# led.net
KiCad netlist of a schematic drawn in Altium Designer
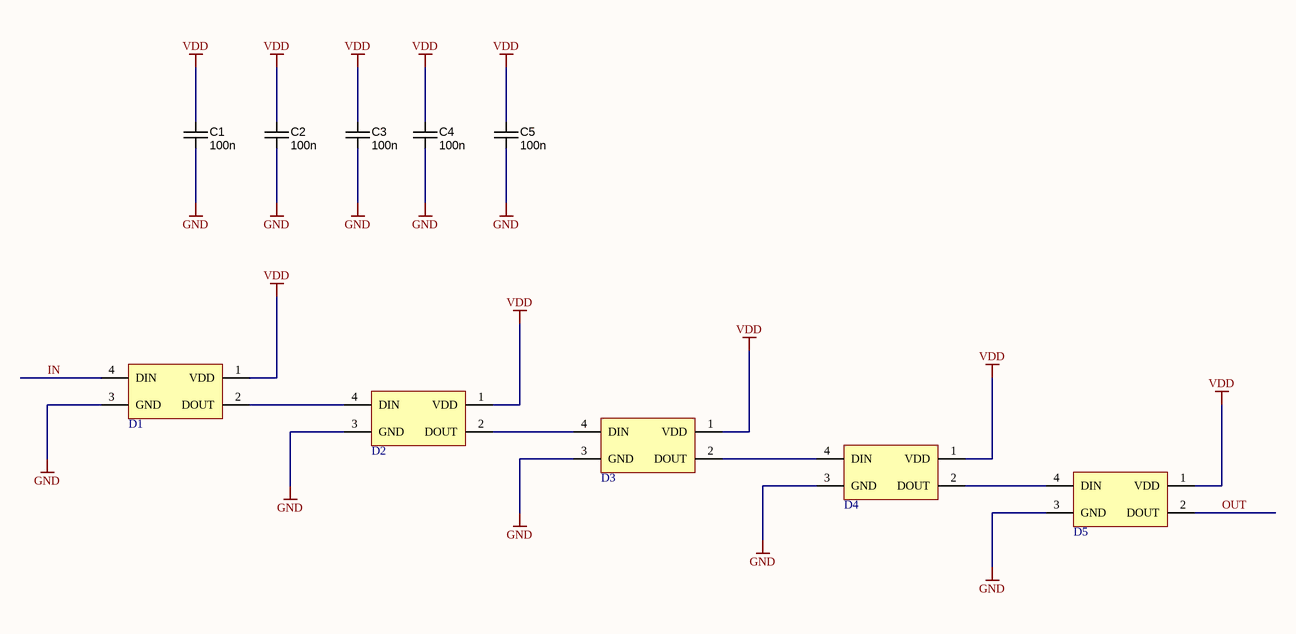
[diagram p0: led.SchDoc]

(export (version "E")
  (design (tool "Eeschema 10.0.6"))
  (components
    (comp (ref "C1")
      (value "100n")
      (footprint "CAPC1608X90N")
      (description "Capacitor SMD Cer 100nF 10% 50V X7R 0603")
      (fields (field (name "TOLERANCE") "±10%") (field (name "Comment") "approved sub OK"))
      (libsource (lib "PBL - Capacitors") (part "CAPC_100n_0603_X7R_50V_10%"))
    )
    (comp (ref "C2")
      (value "100n")
      (footprint "CAPC1608X90N")
      (description "Capacitor SMD Cer 100nF 10% 50V X7R 0603")
      (fields (field (name "TOLERANCE") "±10%") (field (name "Comment") "approved sub OK"))
      (libsource (lib "PBL - Capacitors") (part "CAPC_100n_0603_X7R_50V_10%"))
    )
    (comp (ref "C3")
      (value "100n")
      (footprint "CAPC1608X90N")
      (description "Capacitor SMD Cer 100nF 10% 50V X7R 0603")
      (fields (field (name "TOLERANCE") "±10%") (field (name "Comment") "approved sub OK"))
      (libsource (lib "PBL - Capacitors") (part "CAPC_100n_0603_X7R_50V_10%"))
    )
    (comp (ref "C4")
      (value "100n")
      (footprint "CAPC1608X90N")
      (description "Capacitor SMD Cer 100nF 10% 50V X7R 0603")
      (fields (field (name "TOLERANCE") "±10%") (field (name "Comment") "approved sub OK"))
      (libsource (lib "PBL - Capacitors") (part "CAPC_100n_0603_X7R_50V_10%"))
    )
    (comp (ref "C5")
      (value "100n")
      (footprint "CAPC1608X90N")
      (description "Capacitor SMD Cer 100nF 10% 50V X7R 0603")
      (fields (field (name "TOLERANCE") "±10%") (field (name "Comment") "approved sub OK"))
      (libsource (lib "PBL - Capacitors") (part "CAPC_100n_0603_X7R_50V_10%"))
    )
    (comp (ref "D1")
      (value "LED_5050_WS2812B")
      (footprint "Jarrett:LED_5050_WS2812B")
      (description "LED")
      (libsource (lib "Jarrett") (part "LED_5050_WS2812B"))
    )
    (comp (ref "D2")
      (value "LED_5050_WS2812B")
      (footprint "Jarrett:LED_5050_WS2812B")
      (description "LED")
      (libsource (lib "Jarrett") (part "LED_5050_WS2812B"))
    )
    (comp (ref "D3")
      (value "LED_5050_WS2812B")
      (footprint "Jarrett:LED_5050_WS2812B")
      (description "LED")
      (libsource (lib "Jarrett") (part "LED_5050_WS2812B"))
    )
    (comp (ref "D4")
      (value "LED_5050_WS2812B")
      (footprint "Jarrett:LED_5050_WS2812B")
      (description "LED")
      (libsource (lib "Jarrett") (part "LED_5050_WS2812B"))
    )
    (comp (ref "D5")
      (value "LED_5050_WS2812B")
      (footprint "Jarrett:LED_5050_WS2812B")
      (description "LED")
      (libsource (lib "Jarrett") (part "LED_5050_WS2812B"))
    )
  )
  (nets
    (net (code "1") (name "/IN") (class "Default")
      (node (ref "D1") (pin "4") (pinfunction "DIN_4") (pintype "passive"))
    )
    (net (code "2") (name "/OUT") (class "Default")
      (node (ref "D5") (pin "2") (pinfunction "DOUT_2") (pintype "passive"))
    )
    (net (code "3") (name "GND") (class "Default")
      (node (ref "C1") (pin "2") (pintype "passive"))
      (node (ref "C2") (pin "2") (pintype "passive"))
      (node (ref "C3") (pin "2") (pintype "passive"))
      (node (ref "C4") (pin "2") (pintype "passive"))
      (node (ref "C5") (pin "2") (pintype "passive"))
      (node (ref "D1") (pin "3") (pinfunction "GND_3") (pintype "passive"))
      (node (ref "D2") (pin "3") (pinfunction "GND_3") (pintype "passive"))
      (node (ref "D3") (pin "3") (pinfunction "GND_3") (pintype "passive"))
      (node (ref "D4") (pin "3") (pinfunction "GND_3") (pintype "passive"))
      (node (ref "D5") (pin "3") (pinfunction "GND_3") (pintype "passive"))
    )
    (net (code "4") (name "Net-(D1-DOUT)") (class "Default")
      (node (ref "D1") (pin "2") (pinfunction "DOUT_2") (pintype "passive"))
      (node (ref "D2") (pin "4") (pinfunction "DIN_4") (pintype "passive"))
    )
    (net (code "5") (name "Net-(D2-DOUT)") (class "Default")
      (node (ref "D2") (pin "2") (pinfunction "DOUT_2") (pintype "passive"))
      (node (ref "D3") (pin "4") (pinfunction "DIN_4") (pintype "passive"))
    )
    (net (code "6") (name "Net-(D3-DOUT)") (class "Default")
      (node (ref "D3") (pin "2") (pinfunction "DOUT_2") (pintype "passive"))
      (node (ref "D4") (pin "4") (pinfunction "DIN_4") (pintype "passive"))
    )
    (net (code "7") (name "Net-(D4-DOUT)") (class "Default")
      (node (ref "D4") (pin "2") (pinfunction "DOUT_2") (pintype "passive"))
      (node (ref "D5") (pin "4") (pinfunction "DIN_4") (pintype "passive"))
    )
    (net (code "8") (name "VDD") (class "Default")
      (node (ref "C1") (pin "1") (pintype "passive"))
      (node (ref "C2") (pin "1") (pintype "passive"))
      (node (ref "C3") (pin "1") (pintype "passive"))
      (node (ref "C4") (pin "1") (pintype "passive"))
      (node (ref "C5") (pin "1") (pintype "passive"))
      (node (ref "D1") (pin "1") (pinfunction "VDD_1") (pintype "passive"))
      (node (ref "D2") (pin "1") (pinfunction "VDD_1") (pintype "passive"))
      (node (ref "D3") (pin "1") (pinfunction "VDD_1") (pintype "passive"))
      (node (ref "D4") (pin "1") (pinfunction "VDD_1") (pintype "passive"))
      (node (ref "D5") (pin "1") (pinfunction "VDD_1") (pintype "passive"))
    )
  )
)
